# LCD.net
KiCad netlist of a schematic drawn in EAGLE
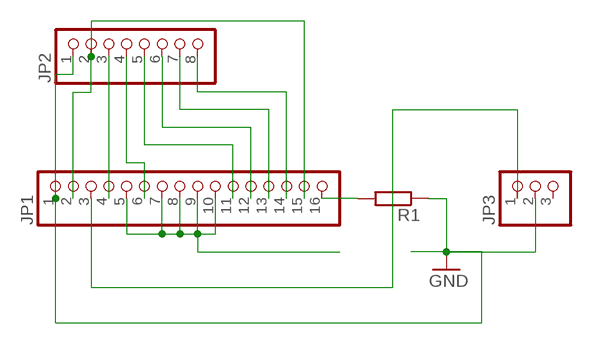
[diagram p0: schematic, sheet 1]

(export (version "E")
  (design (tool "Eeschema 10.0.6"))
  (components
    (comp (ref "JP1")
      (value "PINHD-1X16")
      (footprint "eagle-import:1X16")
      (libsource (lib "eagle-import") (part "PINHD-1X16"))
    )
    (comp (ref "JP2")
      (value "PINHD-1X8")
      (footprint "eagle-import:1X08")
      (libsource (lib "eagle-import") (part "PINHD-1X8"))
    )
    (comp (ref "JP3")
      (value "PINHD-1X3")
      (footprint "eagle-import:1X03")
      (libsource (lib "eagle-import") (part "PINHD-1X3"))
    )
    (comp (ref "R1")
      (value "R-EU_0207/12")
      (footprint "eagle-import:0207_12")
      (libsource (lib "eagle-import") (part "R-EU_0207/12"))
    )
  )
  (nets
    (net (code "1") (name "GND") (class "Default")
      (node (ref "JP1") (pin "1") (pinfunction "1_1") (pintype "passive"))
      (node (ref "JP2") (pin "1") (pinfunction "1_1") (pintype "passive"))
      (node (ref "JP3") (pin "2") (pinfunction "2_2") (pintype "passive"))
      (node (ref "R1") (pin "1") (pinfunction "1_1") (pintype "passive"))
    )
    (net (code "2") (name "Net-(JP1-Pad3)") (class "Default")
      (node (ref "JP1") (pin "3") (pinfunction "3_3") (pintype "passive"))
      (node (ref "JP3") (pin "1") (pinfunction "1_1") (pintype "passive"))
    )
    (net (code "3") (name "Net-(JP1-Pad4)") (class "Default")
      (node (ref "JP1") (pin "4") (pinfunction "4_4") (pintype "passive"))
      (node (ref "JP2") (pin "3") (pinfunction "3_3") (pintype "passive"))
    )
    (net (code "4") (name "Net-(JP1-Pad6)") (class "Default")
      (node (ref "JP1") (pin "6") (pinfunction "6_6") (pintype "passive"))
      (node (ref "JP2") (pin "4") (pinfunction "4_4") (pintype "passive"))
    )
    (net (code "5") (name "Net-(JP1-Pad10)") (class "Default")
      (node (ref "JP1") (pin "10") (pinfunction "10_10") (pintype "passive"))
      (node (ref "JP1") (pin "5") (pinfunction "5_5") (pintype "passive"))
      (node (ref "JP1") (pin "7") (pinfunction "7_7") (pintype "passive"))
      (node (ref "JP1") (pin "8") (pinfunction "8_8") (pintype "passive"))
      (node (ref "JP1") (pin "9") (pinfunction "9_9") (pintype "passive"))
    )
    (net (code "6") (name "Net-(JP1-Pad11)") (class "Default")
      (node (ref "JP1") (pin "11") (pinfunction "11_11") (pintype "passive"))
      (node (ref "JP2") (pin "5") (pinfunction "5_5") (pintype "passive"))
    )
    (net (code "7") (name "Net-(JP1-Pad12)") (class "Default")
      (node (ref "JP1") (pin "12") (pinfunction "12_12") (pintype "passive"))
      (node (ref "JP2") (pin "6") (pinfunction "6_6") (pintype "passive"))
    )
    (net (code "8") (name "Net-(JP1-Pad13)") (class "Default")
      (node (ref "JP1") (pin "13") (pinfunction "13_13") (pintype "passive"))
      (node (ref "JP2") (pin "7") (pinfunction "7_7") (pintype "passive"))
    )
    (net (code "9") (name "Net-(JP1-Pad14)") (class "Default")
      (node (ref "JP1") (pin "14") (pinfunction "14_14") (pintype "passive"))
      (node (ref "JP2") (pin "8") (pinfunction "8_8") (pintype "passive"))
    )
    (net (code "10") (name "Net-(JP1-Pad15)") (class "Default")
      (node (ref "JP1") (pin "15") (pinfunction "15_15") (pintype "passive"))
      (node (ref "JP1") (pin "2") (pinfunction "2_2") (pintype "passive"))
      (node (ref "JP2") (pin "2") (pinfunction "2_2") (pintype "passive"))
    )
    (net (code "11") (name "Net-(JP1-Pad16)") (class "Default")
      (node (ref "JP1") (pin "16") (pinfunction "16_16") (pintype "passive"))
      (node (ref "R1") (pin "2") (pinfunction "2_2") (pintype "passive"))
    )
    (net (code "12") (name "unconnected-(JP3-Pad3)") (class "Default")
      (node (ref "JP3") (pin "3") (pinfunction "3_3") (pintype "passive"))
    )
  )
)
